# Sheet2_usb.net
KiCad netlist of a schematic drawn in Altium Designer
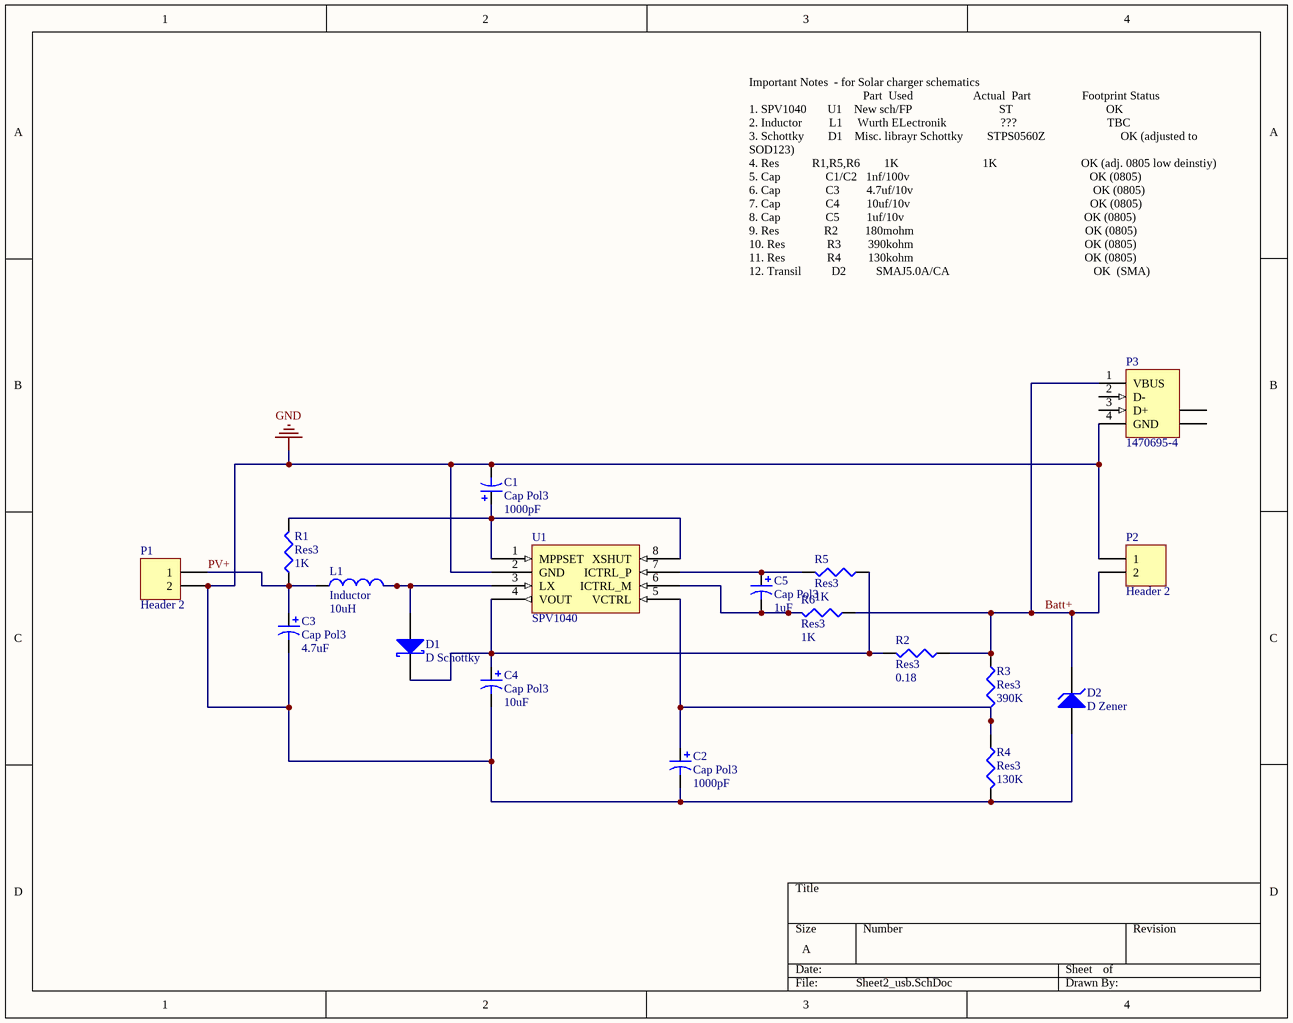
[diagram p0: Sheet2_usb.SchDoc]

(export (version "E")
  (design (tool "Eeschema 10.0.6"))
  (components
    (comp (ref "C1")
      (value "Cap Pol3")
      (footprint "2012[0805]")
      (description "Polarized Capacitor (Surface Mount)")
      (fields (field (name "ALTIUM_VALUE") "1000pF") (field (name "PUBLISHER") "Altium Limited"))
      (libsource (lib "Miscellaneous Devices") (part "Cap Pol3"))
    )
    (comp (ref "C2")
      (value "Cap Pol3")
      (footprint "2012[0805]")
      (description "Polarized Capacitor (Surface Mount)")
      (fields (field (name "ALTIUM_VALUE") "1000pF") (field (name "PUBLISHER") "Altium Limited"))
      (libsource (lib "Miscellaneous Devices") (part "Cap Pol3"))
    )
    (comp (ref "C3")
      (value "Cap Pol3")
      (footprint "2012[0805]")
      (description "Polarized Capacitor (Surface Mount)")
      (fields (field (name "ALTIUM_VALUE") "4.7uF") (field (name "PUBLISHER") "Altium Limited"))
      (libsource (lib "Miscellaneous Devices") (part "Cap Pol3"))
    )
    (comp (ref "C4")
      (value "Cap Pol3")
      (footprint "2012[0805]")
      (description "Polarized Capacitor (Surface Mount)")
      (fields (field (name "ALTIUM_VALUE") "10uF") (field (name "PUBLISHER") "Altium Limited"))
      (libsource (lib "Miscellaneous Devices") (part "Cap Pol3"))
    )
    (comp (ref "C5")
      (value "Cap Pol3")
      (footprint "2012[0805]")
      (description "Polarized Capacitor (Surface Mount)")
      (fields (field (name "ALTIUM_VALUE") "1uF") (field (name "PUBLISHER") "Altium Limited"))
      (libsource (lib "Miscellaneous Devices") (part "Cap Pol3"))
    )
    (comp (ref "D1")
      (value "D Schottky")
      (footprint "SOD123")
      (description "Schottky Diode")
      (fields (field (name "PUBLISHER") "Altium Limited"))
      (libsource (lib "Miscellaneous Devices") (part "D Schottky"))
    )
    (comp (ref "D2")
      (value "D Zener")
      (footprint "DSO-C2/X1.8")
      (description "Zener Diode")
      (fields (field (name "PUBLISHER") "Altium Limited"))
      (libsource (lib "Miscellaneous Devices") (part "D Zener"))
    )
    (comp (ref "L1")
      (value "Inductor")
      (footprint "INDP8181X30N")
      (fields (field (name "ALTIUM_VALUE") "10uH") (field (name "PUBLISHER") "Altium Limited"))
      (libsource (lib "Miscellaneous Devices") (part "Inductor"))
    )
    (comp (ref "P1")
      (value "Header 2")
      (footprint "HDR1X2")
      (description "Header, 2-Pin")
      (fields (field (name "PUBLISHER") "Altium Limited"))
      (libsource (lib "") (part "Header 2_1"))
    )
    (comp (ref "P2")
      (value "Header 2")
      (footprint "HDR1X2")
      (description "Header, 2-Pin")
      (fields (field (name "PUBLISHER") "Altium Limited"))
      (libsource (lib "Miscellaneous Connectors") (part "Header 2"))
    )
    (comp (ref "P3")
      (value "1470695-4")
      (footprint "1470695A")
      (description "USB 1.1, Right Angle, SMT, A Type, Plug, 4 Position, Black")
      (fields (field (name "PUBLISHER") "Altium Limited"))
      (libsource (lib "AMP Serial Bus USB") (part "1470695-4"))
    )
    (comp (ref "R1")
      (value "Res3")
      (footprint "2012[0805]")
      (description "Resistor")
      (fields (field (name "ALTIUM_VALUE") "1K") (field (name "PUBLISHER") "Altium Limited"))
      (libsource (lib "Miscellaneous Devices") (part "Res3"))
    )
    (comp (ref "R2")
      (value "Res3")
      (footprint "2012[0805]")
      (description "Resistor")
      (fields (field (name "ALTIUM_VALUE") "0.18") (field (name "PUBLISHER") "Altium Limited"))
      (libsource (lib "Miscellaneous Devices") (part "Res3"))
    )
    (comp (ref "R3")
      (value "Res3")
      (footprint "2012[0805]")
      (description "Resistor")
      (fields (field (name "ALTIUM_VALUE") "390K") (field (name "PUBLISHER") "Altium Limited"))
      (libsource (lib "Miscellaneous Devices") (part "Res3"))
    )
    (comp (ref "R4")
      (value "Res3")
      (footprint "2012[0805]")
      (description "Resistor")
      (fields (field (name "ALTIUM_VALUE") "130K") (field (name "PUBLISHER") "Altium Limited"))
      (libsource (lib "Miscellaneous Devices") (part "Res3"))
    )
    (comp (ref "R5")
      (value "Res3")
      (footprint "2012[0805]")
      (description "Resistor")
      (fields (field (name "ALTIUM_VALUE") "1K") (field (name "PUBLISHER") "Altium Limited"))
      (libsource (lib "Miscellaneous Devices") (part "Res3"))
    )
    (comp (ref "R6")
      (value "Res3")
      (footprint "2012[0805]")
      (description "Resistor")
      (fields (field (name "ALTIUM_VALUE") "1K") (field (name "PUBLISHER") "Altium Limited"))
      (libsource (lib "Miscellaneous Devices") (part "Res3"))
    )
    (comp (ref "U1")
      (value "SPV1040")
      (footprint "TSOP65P640-8AM")
      (description "MPPT DC DC switcher")
      (libsource (lib "SPV1040T") (part "Component_1"))
    )
  )
  (nets
    (net (code "1") (name "/Batt+") (class "Default")
      (node (ref "D2") (pin "2") (pinfunction "K_2") (pintype "passive"))
      (node (ref "P2") (pin "2") (pinfunction "2_2") (pintype "passive"))
      (node (ref "P3") (pin "1") (pinfunction "VBUS_1") (pintype "power_in"))
      (node (ref "R2") (pin "1") (pinfunction "1_1") (pintype "passive"))
      (node (ref "R3") (pin "1") (pinfunction "1_1") (pintype "passive"))
      (node (ref "R6") (pin "1") (pinfunction "1_1") (pintype "passive"))
    )
    (net (code "2") (name "/PV+") (class "Default")
      (node (ref "C3") (pin "1") (pinfunction "1_1") (pintype "passive"))
      (node (ref "L1") (pin "1") (pinfunction "1_1") (pintype "passive"))
      (node (ref "P1") (pin "1") (pinfunction "1_1") (pintype "passive"))
      (node (ref "R1") (pin "1") (pinfunction "1_1") (pintype "passive"))
    )
    (net (code "3") (name "GND") (class "Default")
      (node (ref "C1") (pin "2") (pinfunction "2_2") (pintype "passive"))
      (node (ref "C2") (pin "2") (pinfunction "2_2") (pintype "passive"))
      (node (ref "C3") (pin "2") (pinfunction "2_2") (pintype "passive"))
      (node (ref "C4") (pin "2") (pinfunction "2_2") (pintype "passive"))
      (node (ref "D2") (pin "1") (pinfunction "A_1") (pintype "passive"))
      (node (ref "P1") (pin "2") (pinfunction "2_2") (pintype "passive"))
      (node (ref "P2") (pin "1") (pinfunction "1_1") (pintype "passive"))
      (node (ref "P3") (pin "4") (pinfunction "GND_4") (pintype "power_in"))
      (node (ref "R4") (pin "2") (pinfunction "2_2") (pintype "passive"))
      (node (ref "U1") (pin "2") (pinfunction "GND_2") (pintype "power_in"))
    )
    (net (code "4") (name "Net-(D1-A)") (class "Default")
      (node (ref "D1") (pin "1") (pinfunction "A_1") (pintype "passive"))
      (node (ref "L1") (pin "2") (pinfunction "2_2") (pintype "passive"))
      (node (ref "U1") (pin "3") (pinfunction "LX_3") (pintype "input"))
    )
    (net (code "5") (name "Net-(D1-K)") (class "Default")
      (node (ref "C4") (pin "1") (pinfunction "1_1") (pintype "passive"))
      (node (ref "D1") (pin "2") (pinfunction "K_2") (pintype "passive"))
      (node (ref "R2") (pin "2") (pinfunction "2_2") (pintype "passive"))
      (node (ref "R5") (pin "1") (pinfunction "1_1") (pintype "passive"))
      (node (ref "U1") (pin "4") (pinfunction "VOUT_4") (pintype "output"))
    )
    (net (code "6") (name "Net-(U1-ICTRL_M)") (class "Default")
      (node (ref "C5") (pin "2") (pinfunction "2_2") (pintype "passive"))
      (node (ref "R6") (pin "2") (pinfunction "2_2") (pintype "passive"))
      (node (ref "U1") (pin "6") (pinfunction "ICTRL_M_6") (pintype "input"))
    )
    (net (code "7") (name "Net-(U1-ICTRL_P)") (class "Default")
      (node (ref "C5") (pin "1") (pinfunction "1_1") (pintype "passive"))
      (node (ref "R5") (pin "2") (pinfunction "2_2") (pintype "passive"))
      (node (ref "U1") (pin "7") (pinfunction "ICTRL_P_7") (pintype "input"))
    )
    (net (code "8") (name "Net-(U1-MPPSET)") (class "Default")
      (node (ref "C1") (pin "1") (pinfunction "1_1") (pintype "passive"))
      (node (ref "R1") (pin "2") (pinfunction "2_2") (pintype "passive"))
      (node (ref "U1") (pin "1") (pinfunction "MPPSET_1") (pintype "input"))
      (node (ref "U1") (pin "8") (pinfunction "XSHUT_8") (pintype "input"))
    )
    (net (code "9") (name "Net-(U1-VCTRL)") (class "Default")
      (node (ref "C2") (pin "1") (pinfunction "1_1") (pintype "passive"))
      (node (ref "R3") (pin "2") (pinfunction "2_2") (pintype "passive"))
      (node (ref "R4") (pin "1") (pinfunction "1_1") (pintype "passive"))
      (node (ref "U1") (pin "5") (pinfunction "VCTRL_5") (pintype "input"))
    )
    (net (code "10") (name "unconnected-(P3-D+-Pad3)") (class "Default")
      (node (ref "P3") (pin "3") (pinfunction "D+_3") (pintype "input"))
    )
    (net (code "11") (name "unconnected-(P3-D--Pad2)") (class "Default")
      (node (ref "P3") (pin "2") (pinfunction "D-_2") (pintype "input"))
    )
    (net (code "12") (name "unconnected-(P3-SHLD-Pad5)") (class "Default")
      (node (ref "P3") (pin "5") (pinfunction "SHLD_5") (pintype "passive"))
    )
    (net (code "13") (name "unconnected-(P3-SHLD-Pad6)") (class "Default")
      (node (ref "P3") (pin "6") (pinfunction "SHLD_6") (pintype "passive"))
    )
  )
)
